# ProPrj_RPI5_tinkling_2026-08-20.net
KiCad netlist of a schematic drawn in EasyEDA Pro
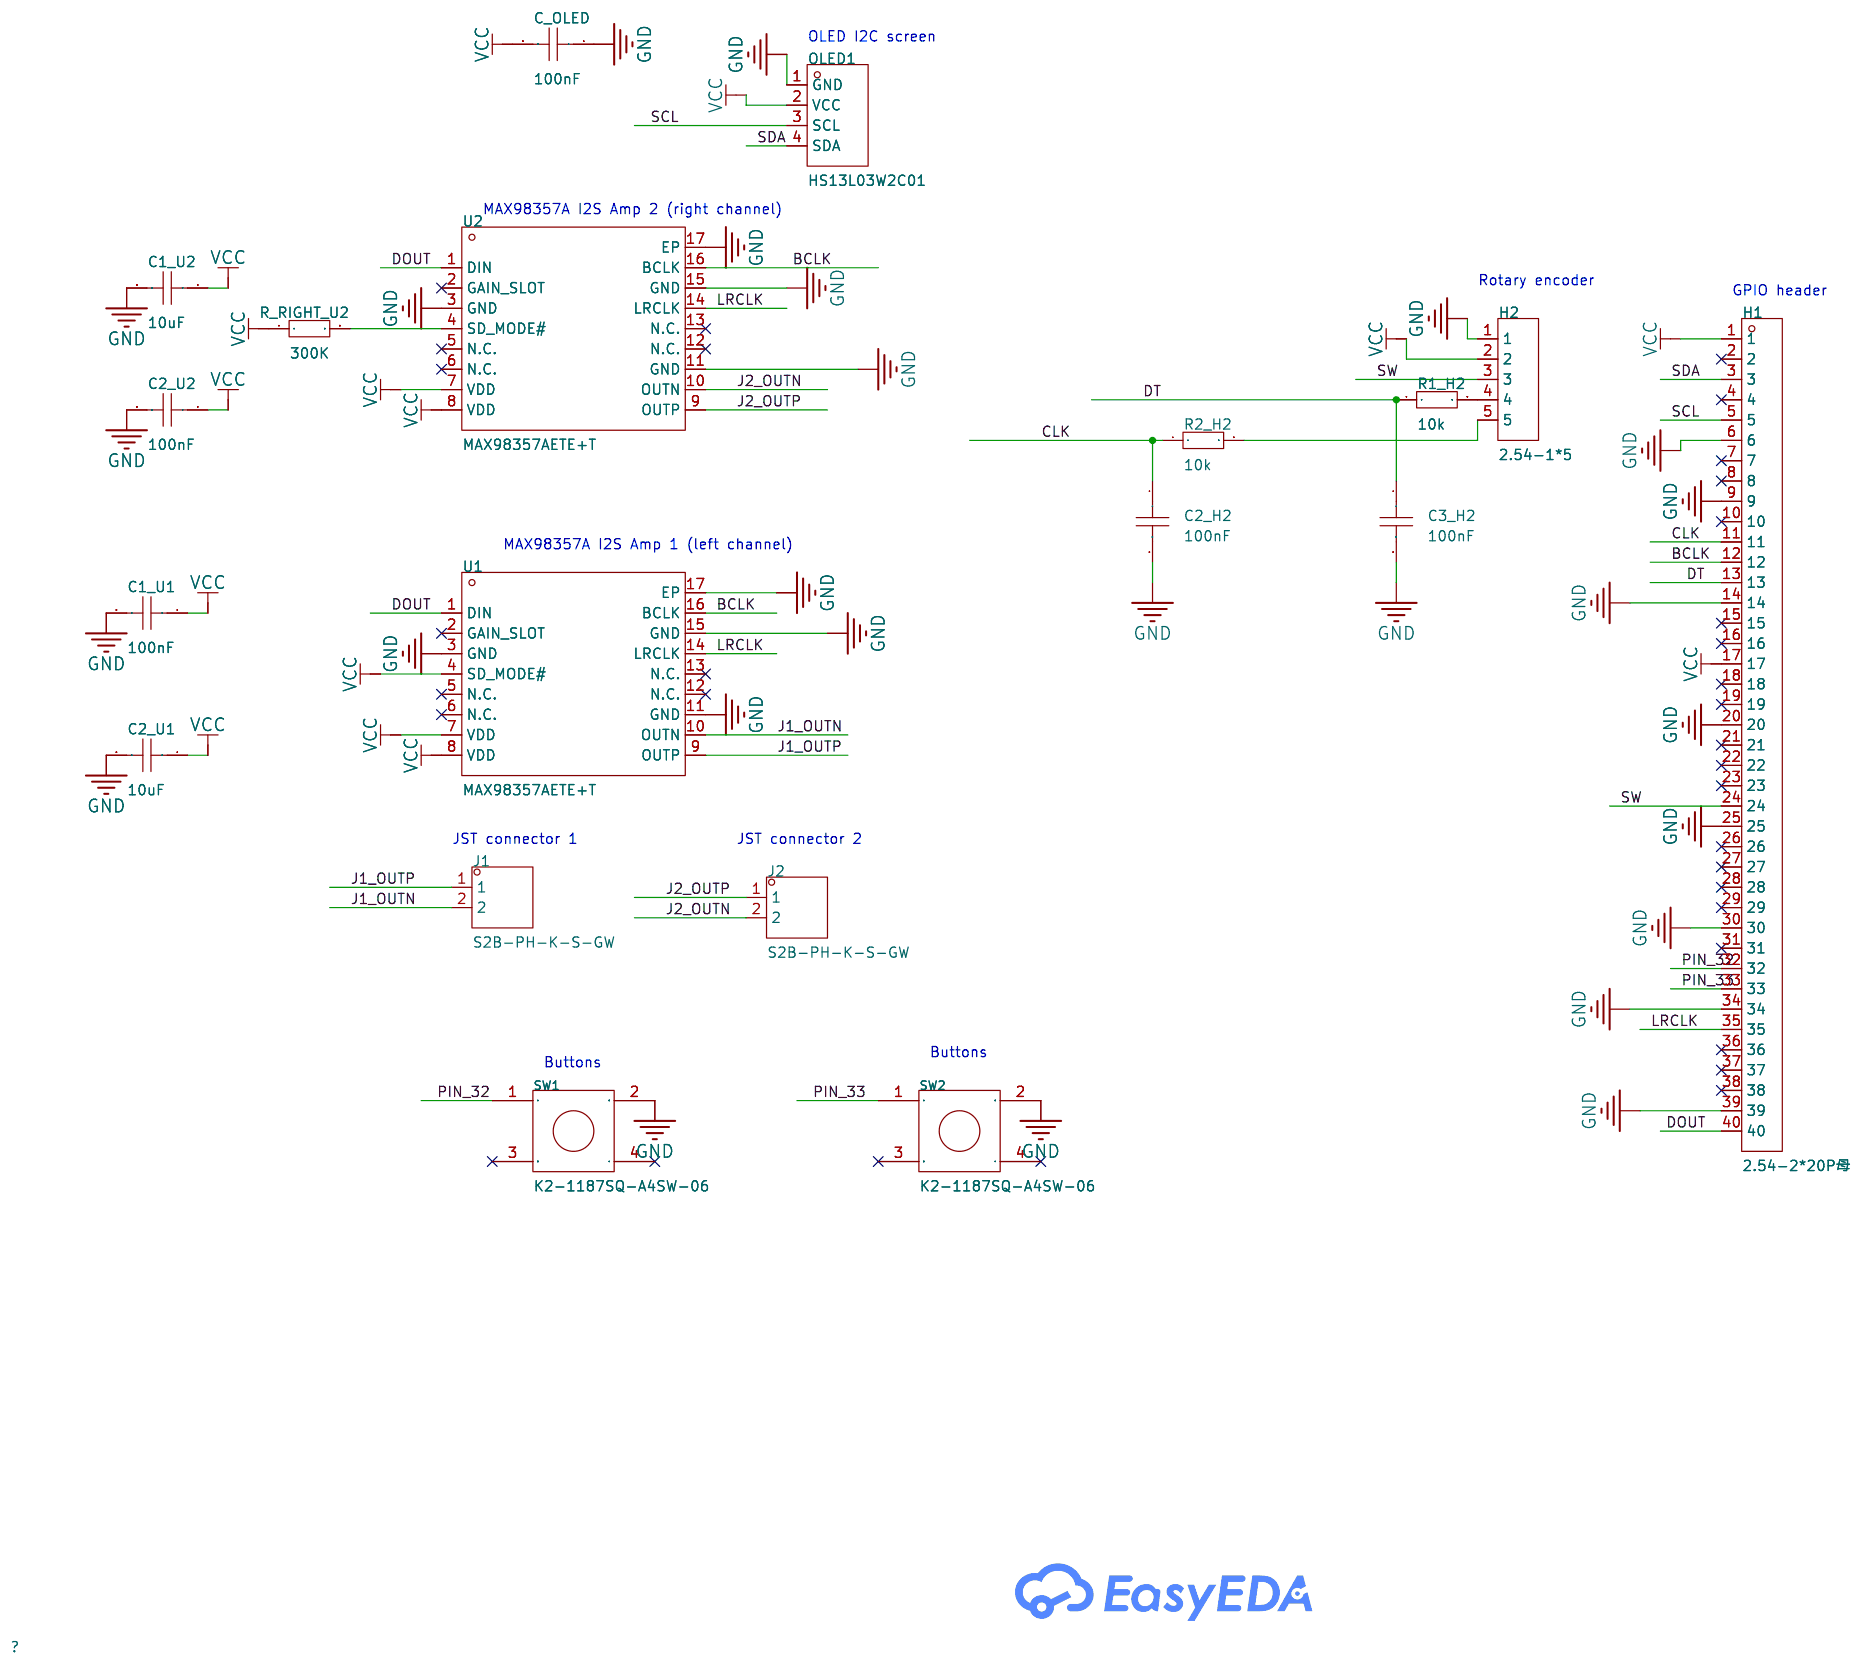
[diagram p0: schematic sheet]

(export (version "E")
  (design (tool "Eeschema 10.0.6"))
  (components
    (comp (ref "C1_U1")
      (value "100nF")
      (footprint "easyedapro:C0603")
      (description "Capacitance:100nF Tolerance:±10% Tolerance:±10% Voltage Rating:16V Temperature Coefficient:X7R")
      (fields
        (field (name "Manufacturer Part") "CL05B104KO5NNNC")
        (field (name "Manufacturer") "SAMSUNG(三星)")
      )
      (libsource (lib "easyedapro") (part "CAP"))
    )
    (comp (ref "C1_U2")
      (value "10uF")
      (footprint "easyedapro:C0603")
      (description "Capacitance:10uF Tolerance:±10% Tolerance:±10% Voltage Rating:25V Temperature Coefficient:X5R")
      (fields
        (field (name "Manufacturer Part") "CL21A106KAYNNNE")
        (field (name "Manufacturer") "SAMSUNG(三星)")
      )
      (libsource (lib "easyedapro") (part "CAP"))
    )
    (comp (ref "C2_H2")
      (value "100nF")
      (footprint "easyedapro:C0603")
      (description "Capacitance:100nF Tolerance:±10% Tolerance:±10% Voltage Rating:25V Temperature Coefficient:X7R")
      (fields
        (field (name "Manufacturer Part") "CL10B104KA8NNNC")
        (field (name "Manufacturer") "SAMSUNG(三星)")
      )
      (libsource (lib "easyedapro") (part "CAP"))
    )
    (comp (ref "C2_U1")
      (value "10uF")
      (footprint "easyedapro:C0603")
      (description "Capacitance:10uF Tolerance:±10% Tolerance:±10% Voltage Rating:25V Temperature Coefficient:X5R")
      (fields
        (field (name "Manufacturer Part") "CL21A106KAYNNNE")
        (field (name "Manufacturer") "SAMSUNG(三星)")
      )
      (libsource (lib "easyedapro") (part "CAP"))
    )
    (comp (ref "C2_U2")
      (value "100nF")
      (footprint "easyedapro:C0603")
      (description "Capacitance:100nF Tolerance:±10% Tolerance:±10% Voltage Rating:16V Temperature Coefficient:X7R")
      (fields
        (field (name "Manufacturer Part") "CL05B104KO5NNNC")
        (field (name "Manufacturer") "SAMSUNG(三星)")
      )
      (libsource (lib "easyedapro") (part "CAP"))
    )
    (comp (ref "C3_H2")
      (value "100nF")
      (footprint "easyedapro:C0603")
      (description "Capacitance:100nF Tolerance:±10% Tolerance:±10% Voltage Rating:25V Temperature Coefficient:X7R")
      (fields
        (field (name "Manufacturer Part") "CL10B104KA8NNNC")
        (field (name "Manufacturer") "SAMSUNG(三星)")
      )
      (libsource (lib "easyedapro") (part "CAP"))
    )
    (comp (ref "C_OLED")
      (value "100nF")
      (footprint "easyedapro:C0603")
      (description "Capacitance:100nF Tolerance:±10% Tolerance:±10% Voltage Rating:25V Temperature Coefficient:X7R")
      (fields
        (field (name "Manufacturer Part") "CL10B104KA8NNNC")
        (field (name "Manufacturer") "SAMSUNG(三星)")
      )
      (libsource (lib "easyedapro") (part "CAP"))
    )
    (comp (ref "H1")
      (value "2.54-2*20P母")
      (footprint "easyedapro:HDR-TH_40P-P2.54-V-F")
      (fields (field (name "Manufacturer") "BOOMELE(博穆精密)"))
      (libsource (lib "easyedapro") (part "2.54MM 1X40T 排母"))
    )
    (comp (ref "H2")
      (value "2.54-1*5")
      (footprint "easyedapro:HDR-TH_5P-P2.54-V-M")
      (fields (field (name "Manufacturer") "ZHOURI(洲日)"))
      (libsource (lib "easyedapro") (part "2.54-1*5"))
    )
    (comp (ref "J1")
      (value "S2B-PH-K-S-GW")
      (footprint "easyedapro:CONN-TH_S2B-PH-K-S-GW")
      (fields (field (name "Manufacturer") "JST"))
      (libsource (lib "easyedapro") (part "S2B-PH-K-S-GW"))
    )
    (comp (ref "J2")
      (value "S2B-PH-K-S-GW")
      (footprint "easyedapro:CONN-TH_S2B-PH-K-S-GW")
      (fields (field (name "Manufacturer") "JST"))
      (libsource (lib "easyedapro") (part "S2B-PH-K-S-GW"))
    )
    (comp (ref "OLED1")
      (value "HS13L03W2C01")
      (footprint "easyedapro:OLED-TH_L35.4-W33.5_HS13L03W2C01")
      (fields (field (name "Manufacturer") "HS(汉昇)"))
      (libsource (lib "easyedapro") (part "HS13L03W2C01"))
    )
    (comp (ref "R1_H2")
      (value "10k")
      (footprint "easyedapro:R0603")
      (libsource (lib "easyedapro") (part "Res"))
    )
    (comp (ref "R2_H2")
      (value "10k")
      (footprint "easyedapro:R0603")
      (libsource (lib "easyedapro") (part "Res"))
    )
    (comp (ref "R_RIGHT_U2")
      (value "300K")
      (footprint "easyedapro:R0603")
      (libsource (lib "easyedapro") (part "Res"))
    )
    (comp (ref "SW1")
      (value "K2-1187SQ-A4SW-06")
      (footprint "easyedapro:KEY-SMD_4P-L5.2-W5.2-P3.70-LS6.4")
      (fields (field (name "Manufacturer") "韩国韩荣"))
      (libsource (lib "easyedapro") (part "K2-1187SQ-A4SW"))
    )
    (comp (ref "SW2")
      (value "K2-1187SQ-A4SW-06")
      (footprint "easyedapro:KEY-SMD_4P-L5.2-W5.2-P3.70-LS6.4")
      (fields (field (name "Manufacturer") "韩国韩荣"))
      (libsource (lib "easyedapro") (part "K2-1187SQ-A4SW"))
    )
    (comp (ref "U1")
      (value "MAX98357AETE+T")
      (footprint "easyedapro:TQFN-16_L3.0-W3.0-P0.50-BL-EP1.1")
      (fields (field (name "Manufacturer") "ADI(亚德诺)/MAXIM(美信)"))
      (libsource (lib "easyedapro") (part "MAX98357AETE+T_C20745475"))
    )
    (comp (ref "U2")
      (value "MAX98357AETE+T")
      (footprint "easyedapro:TQFN-16_L3.0-W3.0-P0.50-BL-EP1.1")
      (fields (field (name "Manufacturer") "ADI(亚德诺)/MAXIM(美信)"))
      (libsource (lib "easyedapro") (part "MAX98357AETE+T_C20745475"))
    )
  )
  (nets
    (net (code "1") (name "/BCLK") (class "Default")
      (node (ref "H1") (pin "12") (pinfunction "12_12") (pintype "unspecified"))
      (node (ref "U1") (pin "16") (pinfunction "BCLK_16") (pintype "unspecified"))
      (node (ref "U2") (pin "16") (pinfunction "BCLK_16") (pintype "unspecified"))
    )
    (net (code "2") (name "/CLK") (class "Default")
      (node (ref "C2_H2") (pin "1") (pinfunction "1_1") (pintype "input"))
      (node (ref "H1") (pin "11") (pinfunction "11_11") (pintype "unspecified"))
      (node (ref "R2_H2") (pin "1") (pinfunction "1_1") (pintype "input"))
    )
    (net (code "3") (name "/DOUT") (class "Default")
      (node (ref "H1") (pin "40") (pinfunction "40_40") (pintype "unspecified"))
      (node (ref "U1") (pin "1") (pinfunction "DIN_1") (pintype "unspecified"))
      (node (ref "U2") (pin "1") (pinfunction "DIN_1") (pintype "unspecified"))
    )
    (net (code "4") (name "/DT") (class "Default")
      (node (ref "C3_H2") (pin "1") (pinfunction "1_1") (pintype "input"))
      (node (ref "H1") (pin "13") (pinfunction "13_13") (pintype "unspecified"))
      (node (ref "R1_H2") (pin "1") (pinfunction "1_1") (pintype "input"))
    )
    (net (code "5") (name "/J1_OUTN") (class "Default")
      (node (ref "J1") (pin "2") (pinfunction "2_2") (pintype "unspecified"))
      (node (ref "U1") (pin "10") (pinfunction "OUTN_10") (pintype "unspecified"))
    )
    (net (code "6") (name "/J1_OUTP") (class "Default")
      (node (ref "J1") (pin "1") (pinfunction "1_1") (pintype "unspecified"))
      (node (ref "U1") (pin "9") (pinfunction "OUTP_9") (pintype "unspecified"))
    )
    (net (code "7") (name "/J2_OUTN") (class "Default")
      (node (ref "J2") (pin "2") (pinfunction "2_2") (pintype "unspecified"))
      (node (ref "U2") (pin "10") (pinfunction "OUTN_10") (pintype "unspecified"))
    )
    (net (code "8") (name "/J2_OUTP") (class "Default")
      (node (ref "J2") (pin "1") (pinfunction "1_1") (pintype "unspecified"))
      (node (ref "U2") (pin "9") (pinfunction "OUTP_9") (pintype "unspecified"))
    )
    (net (code "9") (name "/LRCLK") (class "Default")
      (node (ref "H1") (pin "35") (pinfunction "35_35") (pintype "unspecified"))
      (node (ref "U1") (pin "14") (pinfunction "LRCLK_14") (pintype "unspecified"))
      (node (ref "U2") (pin "14") (pinfunction "LRCLK_14") (pintype "unspecified"))
    )
    (net (code "10") (name "/PIN_32") (class "Default")
      (node (ref "H1") (pin "32") (pinfunction "32_32") (pintype "unspecified"))
      (node (ref "SW1") (pin "1") (pinfunction "1_1") (pintype "input"))
    )
    (net (code "11") (name "/PIN_33") (class "Default")
      (node (ref "H1") (pin "33") (pinfunction "33_33") (pintype "unspecified"))
      (node (ref "SW2") (pin "1") (pinfunction "1_1") (pintype "input"))
    )
    (net (code "12") (name "/SCL") (class "Default")
      (node (ref "H1") (pin "5") (pinfunction "5_5") (pintype "unspecified"))
      (node (ref "OLED1") (pin "3") (pinfunction "SCL_3") (pintype "unspecified"))
    )
    (net (code "13") (name "/SDA") (class "Default")
      (node (ref "H1") (pin "3") (pinfunction "3_3") (pintype "unspecified"))
      (node (ref "OLED1") (pin "4") (pinfunction "SDA_4") (pintype "unspecified"))
    )
    (net (code "14") (name "/SW") (class "Default")
      (node (ref "H1") (pin "24") (pinfunction "24_24") (pintype "unspecified"))
      (node (ref "H2") (pin "3") (pinfunction "3_3") (pintype "unspecified"))
    )
    (net (code "15") (name "GND") (class "Default")
      (node (ref "C1_U1") (pin "2") (pinfunction "2_2") (pintype "input"))
      (node (ref "C1_U2") (pin "2") (pinfunction "2_2") (pintype "input"))
      (node (ref "C2_H2") (pin "2") (pinfunction "2_2") (pintype "input"))
      (node (ref "C2_U1") (pin "2") (pinfunction "2_2") (pintype "input"))
      (node (ref "C2_U2") (pin "2") (pinfunction "2_2") (pintype "input"))
      (node (ref "C3_H2") (pin "2") (pinfunction "2_2") (pintype "input"))
      (node (ref "C_OLED") (pin "1") (pinfunction "1_1") (pintype "input"))
      (node (ref "H1") (pin "14") (pinfunction "14_14") (pintype "unspecified"))
      (node (ref "H1") (pin "20") (pinfunction "20_20") (pintype "unspecified"))
      (node (ref "H1") (pin "25") (pinfunction "25_25") (pintype "unspecified"))
      (node (ref "H1") (pin "30") (pinfunction "30_30") (pintype "unspecified"))
      (node (ref "H1") (pin "34") (pinfunction "34_34") (pintype "unspecified"))
      (node (ref "H1") (pin "39") (pinfunction "39_39") (pintype "unspecified"))
      (node (ref "H1") (pin "6") (pinfunction "6_6") (pintype "unspecified"))
      (node (ref "H1") (pin "9") (pinfunction "9_9") (pintype "unspecified"))
      (node (ref "H2") (pin "1") (pinfunction "1_1") (pintype "unspecified"))
      (node (ref "OLED1") (pin "1") (pinfunction "GND_1") (pintype "unspecified"))
      (node (ref "SW1") (pin "2") (pinfunction "2_2") (pintype "input"))
      (node (ref "SW2") (pin "2") (pinfunction "2_2") (pintype "input"))
      (node (ref "U1") (pin "11") (pinfunction "GND_11") (pintype "unspecified"))
      (node (ref "U1") (pin "15") (pinfunction "GND_15") (pintype "unspecified"))
      (node (ref "U1") (pin "17") (pinfunction "EP_17") (pintype "unspecified"))
      (node (ref "U1") (pin "3") (pinfunction "GND_3") (pintype "unspecified"))
      (node (ref "U2") (pin "11") (pinfunction "GND_11") (pintype "unspecified"))
      (node (ref "U2") (pin "15") (pinfunction "GND_15") (pintype "unspecified"))
      (node (ref "U2") (pin "17") (pinfunction "EP_17") (pintype "unspecified"))
      (node (ref "U2") (pin "3") (pinfunction "GND_3") (pintype "unspecified"))
    )
    (net (code "16") (name "Net-(H2-Pad4)") (class "Default")
      (node (ref "H2") (pin "4") (pinfunction "4_4") (pintype "unspecified"))
      (node (ref "R1_H2") (pin "2") (pinfunction "2_2") (pintype "input"))
    )
    (net (code "17") (name "Net-(H2-Pad5)") (class "Default")
      (node (ref "H2") (pin "5") (pinfunction "5_5") (pintype "unspecified"))
      (node (ref "R2_H2") (pin "2") (pinfunction "2_2") (pintype "input"))
    )
    (net (code "18") (name "Net-(U2-SD_MODE#)") (class "Default")
      (node (ref "R_RIGHT_U2") (pin "2") (pinfunction "2_2") (pintype "input"))
      (node (ref "U2") (pin "4") (pinfunction "SD_MODE#_4") (pintype "unspecified"))
    )
    (net (code "19") (name "VCC") (class "Default")
      (node (ref "C1_U1") (pin "1") (pinfunction "1_1") (pintype "input"))
      (node (ref "C1_U2") (pin "1") (pinfunction "1_1") (pintype "input"))
      (node (ref "C2_U1") (pin "1") (pinfunction "1_1") (pintype "input"))
      (node (ref "C2_U2") (pin "1") (pinfunction "1_1") (pintype "input"))
      (node (ref "C_OLED") (pin "2") (pinfunction "2_2") (pintype "input"))
      (node (ref "H1") (pin "1") (pinfunction "1_1") (pintype "unspecified"))
      (node (ref "H1") (pin "17") (pinfunction "17_17") (pintype "unspecified"))
      (node (ref "H2") (pin "2") (pinfunction "2_2") (pintype "unspecified"))
      (node (ref "OLED1") (pin "2") (pinfunction "VCC_2") (pintype "unspecified"))
      (node (ref "R_RIGHT_U2") (pin "1") (pinfunction "1_1") (pintype "input"))
      (node (ref "U1") (pin "4") (pinfunction "SD_MODE#_4") (pintype "unspecified"))
      (node (ref "U1") (pin "7") (pinfunction "VDD_7") (pintype "unspecified"))
      (node (ref "U1") (pin "8") (pinfunction "VDD_8") (pintype "unspecified"))
      (node (ref "U2") (pin "7") (pinfunction "VDD_7") (pintype "unspecified"))
      (node (ref "U2") (pin "8") (pinfunction "VDD_8") (pintype "unspecified"))
    )
    (net (code "20") (name "unconnected-(H1-Pad2)") (class "Default")
      (node (ref "H1") (pin "2") (pinfunction "2_2") (pintype "unspecified+no_connect"))
    )
    (net (code "21") (name "unconnected-(H1-Pad4)") (class "Default")
      (node (ref "H1") (pin "4") (pinfunction "4_4") (pintype "unspecified+no_connect"))
    )
    (net (code "22") (name "unconnected-(H1-Pad7)") (class "Default")
      (node (ref "H1") (pin "7") (pinfunction "7_7") (pintype "unspecified+no_connect"))
    )
    (net (code "23") (name "unconnected-(H1-Pad8)") (class "Default")
      (node (ref "H1") (pin "8") (pinfunction "8_8") (pintype "unspecified+no_connect"))
    )
    (net (code "24") (name "unconnected-(H1-Pad10)") (class "Default")
      (node (ref "H1") (pin "10") (pinfunction "10_10") (pintype "unspecified+no_connect"))
    )
    (net (code "25") (name "unconnected-(H1-Pad15)") (class "Default")
      (node (ref "H1") (pin "15") (pinfunction "15_15") (pintype "unspecified+no_connect"))
    )
    (net (code "26") (name "unconnected-(H1-Pad16)") (class "Default")
      (node (ref "H1") (pin "16") (pinfunction "16_16") (pintype "unspecified+no_connect"))
    )
    (net (code "27") (name "unconnected-(H1-Pad18)") (class "Default")
      (node (ref "H1") (pin "18") (pinfunction "18_18") (pintype "unspecified+no_connect"))
    )
    (net (code "28") (name "unconnected-(H1-Pad19)") (class "Default")
      (node (ref "H1") (pin "19") (pinfunction "19_19") (pintype "unspecified+no_connect"))
    )
    (net (code "29") (name "unconnected-(H1-Pad21)") (class "Default")
      (node (ref "H1") (pin "21") (pinfunction "21_21") (pintype "unspecified+no_connect"))
    )
    (net (code "30") (name "unconnected-(H1-Pad22)") (class "Default")
      (node (ref "H1") (pin "22") (pinfunction "22_22") (pintype "unspecified+no_connect"))
    )
    (net (code "31") (name "unconnected-(H1-Pad23)") (class "Default")
      (node (ref "H1") (pin "23") (pinfunction "23_23") (pintype "unspecified+no_connect"))
    )
    (net (code "32") (name "unconnected-(H1-Pad26)") (class "Default")
      (node (ref "H1") (pin "26") (pinfunction "26_26") (pintype "unspecified+no_connect"))
    )
    (net (code "33") (name "unconnected-(H1-Pad27)") (class "Default")
      (node (ref "H1") (pin "27") (pinfunction "27_27") (pintype "unspecified+no_connect"))
    )
    (net (code "34") (name "unconnected-(H1-Pad28)") (class "Default")
      (node (ref "H1") (pin "28") (pinfunction "28_28") (pintype "unspecified+no_connect"))
    )
    (net (code "35") (name "unconnected-(H1-Pad29)") (class "Default")
      (node (ref "H1") (pin "29") (pinfunction "29_29") (pintype "unspecified+no_connect"))
    )
    (net (code "36") (name "unconnected-(H1-Pad31)") (class "Default")
      (node (ref "H1") (pin "31") (pinfunction "31_31") (pintype "unspecified+no_connect"))
    )
    (net (code "37") (name "unconnected-(H1-Pad36)") (class "Default")
      (node (ref "H1") (pin "36") (pinfunction "36_36") (pintype "unspecified+no_connect"))
    )
    (net (code "38") (name "unconnected-(H1-Pad37)") (class "Default")
      (node (ref "H1") (pin "37") (pinfunction "37_37") (pintype "unspecified+no_connect"))
    )
    (net (code "39") (name "unconnected-(H1-Pad38)") (class "Default")
      (node (ref "H1") (pin "38") (pinfunction "38_38") (pintype "unspecified+no_connect"))
    )
    (net (code "40") (name "unconnected-(SW1-Pad3)") (class "Default")
      (node (ref "SW1") (pin "3") (pinfunction "3_3") (pintype "input+no_connect"))
    )
    (net (code "41") (name "unconnected-(SW1-Pad4)") (class "Default")
      (node (ref "SW1") (pin "4") (pinfunction "4_4") (pintype "input+no_connect"))
    )
    (net (code "42") (name "unconnected-(SW2-Pad3)") (class "Default")
      (node (ref "SW2") (pin "3") (pinfunction "3_3") (pintype "input+no_connect"))
    )
    (net (code "43") (name "unconnected-(SW2-Pad4)") (class "Default")
      (node (ref "SW2") (pin "4") (pinfunction "4_4") (pintype "input+no_connect"))
    )
    (net (code "44") (name "unconnected-(U1-GAIN_SLOT-Pad2)") (class "Default")
      (node (ref "U1") (pin "2") (pinfunction "GAIN_SLOT_2") (pintype "unspecified+no_connect"))
    )
    (net (code "45") (name "unconnected-(U1-N.C.-Pad5)") (class "Default")
      (node (ref "U1") (pin "5") (pinfunction "N.C._5") (pintype "unspecified+no_connect"))
    )
    (net (code "46") (name "unconnected-(U1-N.C.-Pad6)") (class "Default")
      (node (ref "U1") (pin "6") (pinfunction "N.C._6") (pintype "unspecified+no_connect"))
    )
    (net (code "47") (name "unconnected-(U1-N.C.-Pad12)") (class "Default")
      (node (ref "U1") (pin "12") (pinfunction "N.C._12") (pintype "unspecified+no_connect"))
    )
    (net (code "48") (name "unconnected-(U1-N.C.-Pad13)") (class "Default")
      (node (ref "U1") (pin "13") (pinfunction "N.C._13") (pintype "unspecified+no_connect"))
    )
    (net (code "49") (name "unconnected-(U2-GAIN_SLOT-Pad2)") (class "Default")
      (node (ref "U2") (pin "2") (pinfunction "GAIN_SLOT_2") (pintype "unspecified+no_connect"))
    )
    (net (code "50") (name "unconnected-(U2-N.C.-Pad5)") (class "Default")
      (node (ref "U2") (pin "5") (pinfunction "N.C._5") (pintype "unspecified+no_connect"))
    )
    (net (code "51") (name "unconnected-(U2-N.C.-Pad6)") (class "Default")
      (node (ref "U2") (pin "6") (pinfunction "N.C._6") (pintype "unspecified+no_connect"))
    )
    (net (code "52") (name "unconnected-(U2-N.C.-Pad12)") (class "Default")
      (node (ref "U2") (pin "12") (pinfunction "N.C._12") (pintype "unspecified+no_connect"))
    )
    (net (code "53") (name "unconnected-(U2-N.C.-Pad13)") (class "Default")
      (node (ref "U2") (pin "13") (pinfunction "N.C._13") (pintype "unspecified+no_connect"))
    )
  )
)
